# GR_Alim_Puissance.net
KiCad netlist of a schematic drawn in Altium Designer
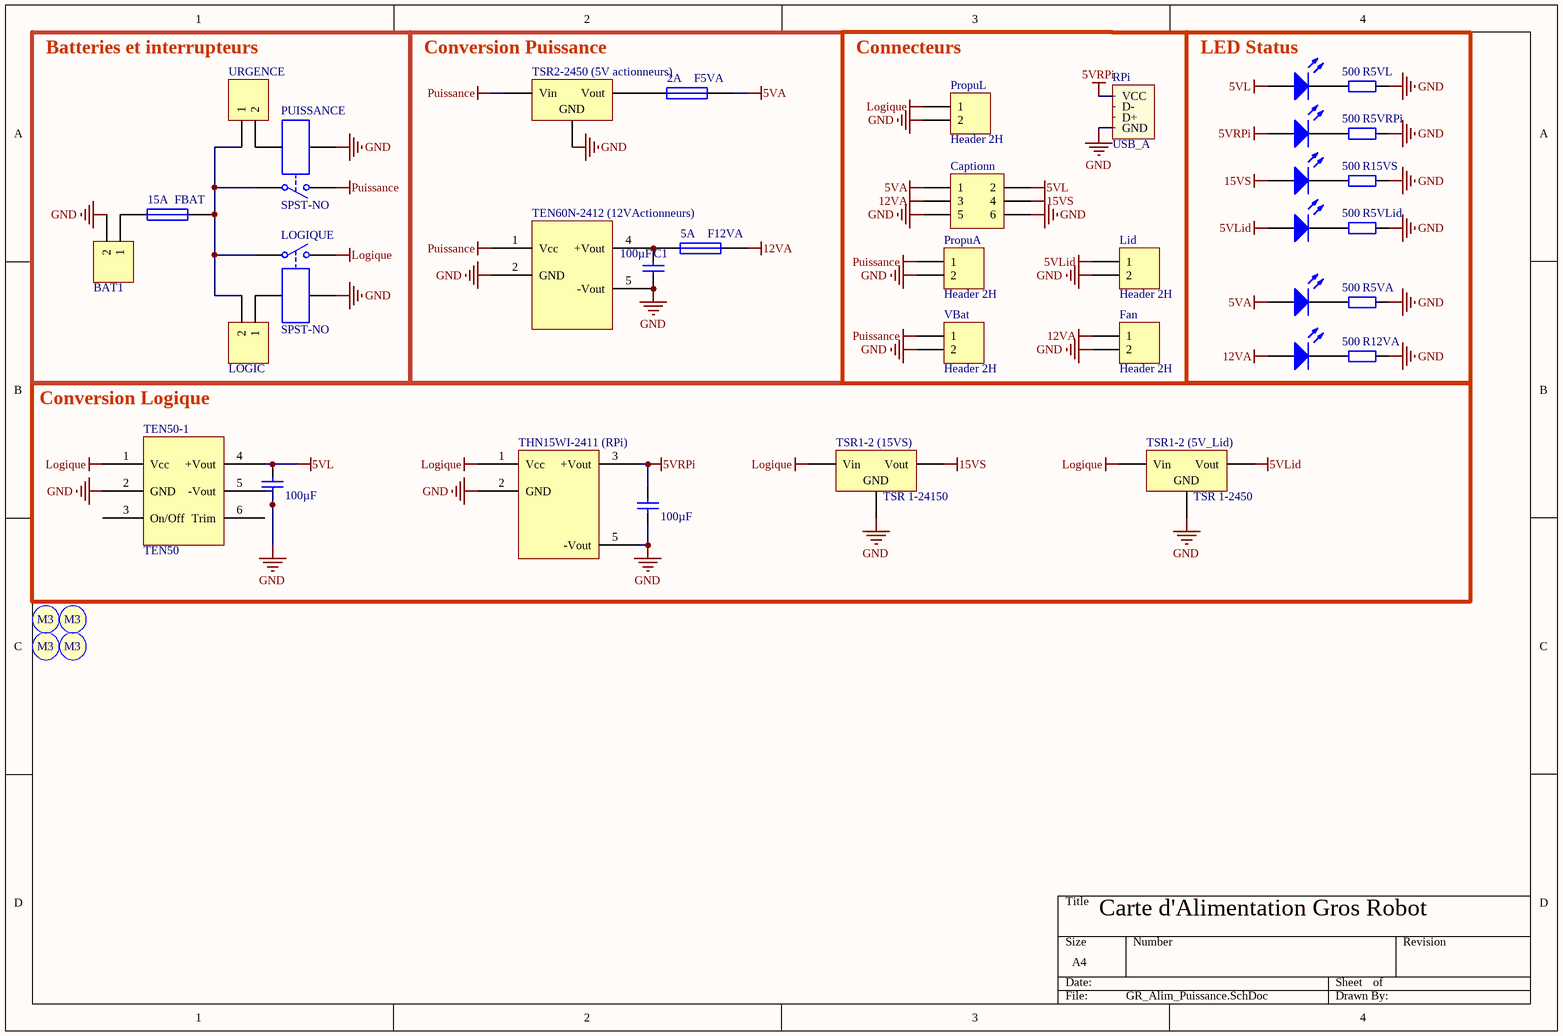
[diagram p0: GR_Alim_Puissance.SchDoc]

(export (version "E")
  (design (tool "Eeschema 10.0.6"))
  (components
    (comp (ref "BAT1")
      (value "Batterie 1")
      (footprint "Battery SALE")
      (description "Header, 2-Pin")
      (fields (field (name "PUBLISHER") "Altium Limited"))
      (libsource (lib "Miscellaneous Connectors") (part "Header 2"))
    )
    (comp (ref "C1")
      (value "100µF")
      (footprint "robot:Condensateur")
      (description "Capacitor")
      (fields (field (name "Comment") "Cap") (field (name "PUBLISHER") "Altium Limited"))
      (libsource (lib "Miscellaneous Devices") (part "Cap"))
    )
    (comp (ref "C10")
      (value "100µF")
      (footprint "robot:Condensateur")
      (description "Capacitor")
      (fields (field (name "Comment") "Cap") (field (name "PUBLISHER") "Altium Limited"))
      (libsource (lib "Miscellaneous Devices") (part "Cap"))
    )
    (comp (ref "C20")
      (value "100µF")
      (footprint "robot:Condensateur")
      (description "Capacitor")
      (fields (field (name "Comment") "Cap") (field (name "PUBLISHER") "Altium Limited"))
      (libsource (lib "Miscellaneous Devices") (part "Cap"))
    )
    (comp (ref "Captionn")
      (value "Header 3X2")
      (footprint "robot:MOLEX_MINIFITJR_3X2")
      (description "Header, 3-Pin, Dual row")
      (fields (field (name "PUBLISHER") "Altium Limited"))
      (libsource (lib "Miscellaneous Connectors") (part "Header 3X2"))
    )
    (comp (ref "D1")
      (value "LED Logique 5V")
      (footprint "3.2X1.6X1.1")
      (description "Typical RED, GREEN, YELLOW, AMBER GaAs LED")
      (fields (field (name "PUBLISHER") "Altium Limited"))
      (libsource (lib "Miscellaneous Devices") (part "LED2"))
    )
    (comp (ref "D2")
      (value "LED RPi 5V")
      (footprint "3.2X1.6X1.1")
      (description "Typical RED, GREEN, YELLOW, AMBER GaAs LED")
      (fields (field (name "PUBLISHER") "Altium Limited"))
      (libsource (lib "Miscellaneous Devices") (part "LED2"))
    )
    (comp (ref "D3")
      (value "LED Sonars 15V")
      (footprint "3.2X1.6X1.1")
      (description "Typical RED, GREEN, YELLOW, AMBER GaAs LED")
      (fields (field (name "PUBLISHER") "Altium Limited"))
      (libsource (lib "Miscellaneous Devices") (part "LED2"))
    )
    (comp (ref "D4")
      (value "LED Actionneurs 5V")
      (footprint "3.2X1.6X1.1")
      (description "Typical RED, GREEN, YELLOW, AMBER GaAs LED")
      (fields (field (name "PUBLISHER") "Altium Limited"))
      (libsource (lib "Miscellaneous Devices") (part "LED2"))
    )
    (comp (ref "D5")
      (value "LED Actionneurs 12V")
      (footprint "3.2X1.6X1.1")
      (description "Typical RED, GREEN, YELLOW, AMBER GaAs LED")
      (fields (field (name "PUBLISHER") "Altium Limited"))
      (libsource (lib "Miscellaneous Devices") (part "LED2"))
    )
    (comp (ref "D6")
      (value "LED Actionneurs 12V")
      (footprint "3.2X1.6X1.1")
      (description "Typical RED, GREEN, YELLOW, AMBER GaAs LED")
      (fields (field (name "PUBLISHER") "Altium Limited"))
      (libsource (lib "Miscellaneous Devices") (part "LED2"))
    )
    (comp (ref "F5VA")
      (value "2A")
      (footprint "robot:Fuse")
      (description "Fuse")
      (fields (field (name "PUBLISHER") "Altium Limited"))
      (libsource (lib "Miscellaneous Devices") (part "Fuse 1"))
    )
    (comp (ref "F12VA")
      (value "5A")
      (footprint "robot:Fuse")
      (description "Fuse")
      (fields (field (name "PUBLISHER") "Altium Limited"))
      (libsource (lib "Miscellaneous Devices") (part "Fuse 1"))
    )
    (comp (ref "Fan")
      (value "Header 2H")
      (footprint "robot:Molex SPOX 2x1H")
      (description "Header, 2-Pin, Right Angle")
      (fields (field (name "PUBLISHER") "Altium Limited"))
      (libsource (lib "Miscellaneous Connectors") (part "Header 2H"))
    )
    (comp (ref "FBAT")
      (value "15A")
      (footprint "robot:Fuse")
      (description "Fuse")
      (fields (field (name "PUBLISHER") "Altium Limited"))
      (libsource (lib "Miscellaneous Devices") (part "Fuse 1"))
    )
    (comp (ref "Lid")
      (value "Header 2H")
      (footprint "robot:Molex_MiniFitJr_2x1H")
      (description "Header, 2-Pin, Right Angle")
      (fields (field (name "PUBLISHER") "Altium Limited"))
      (libsource (lib "Miscellaneous Connectors") (part "Header 2H"))
    )
    (comp (ref "LOGIC")
      (value "Logic")
      (footprint "robot:MOLEX KK254 2X1H M")
      (description "Header, 2-Pin")
      (fields (field (name "PUBLISHER") "Altium Limited"))
      (libsource (lib "Miscellaneous Connectors") (part "Header 2"))
    )
    (comp (ref "LOGIQUE")
      (value "SPST-NO")
      (footprint "Relay")
      (description "OJ-SS-124LMH2,005")
      (fields (field (name "PUBLISHER") "Altium Limited"))
      (libsource (lib "Miscellaneous Devices") (part "Relay-SPST"))
    )
    (comp (ref "PropuA")
      (value "Header 2H")
      (footprint "robot:Molex_MiniFitJr_2x1H")
      (description "Header, 2-Pin, Right Angle")
      (fields (field (name "PUBLISHER") "Altium Limited"))
      (libsource (lib "Miscellaneous Connectors") (part "Header 2H"))
    )
    (comp (ref "PropuL")
      (value "Header 2H")
      (footprint "robot:Molex_MiniFitJr_2x1H")
      (description "Header, 2-Pin, Right Angle")
      (fields (field (name "PUBLISHER") "Altium Limited"))
      (libsource (lib "Miscellaneous Connectors") (part "Header 2H"))
    )
    (comp (ref "PUISSANCE")
      (value "SPST-NO")
      (footprint "Relay")
      (description "OJ-SS-124LMH2,005")
      (fields (field (name "PUBLISHER") "Altium Limited"))
      (libsource (lib "Miscellaneous Devices") (part "Relay-SPST"))
    )
    (comp (ref "R5VA")
      (value "500")
      (footprint "3.2X1.6X1.1")
      (description "Resistor")
      (fields (field (name "Comment") "Res4") (field (name "PUBLISHER") "Altium Limited"))
      (libsource (lib "Miscellaneous Devices") (part "Res2"))
    )
    (comp (ref "R5VL")
      (value "500")
      (footprint "3.2X1.6X1.1")
      (description "Resistor")
      (fields (field (name "Comment") "Res1") (field (name "PUBLISHER") "Altium Limited"))
      (libsource (lib "Miscellaneous Devices") (part "Res2"))
    )
    (comp (ref "R5VLid")
      (value "500")
      (footprint "3.2X1.6X1.1")
      (description "Resistor")
      (fields (field (name "Comment") "Res5") (field (name "PUBLISHER") "Altium Limited"))
      (libsource (lib "Miscellaneous Devices") (part "Res2"))
    )
    (comp (ref "R5VRPi")
      (value "500")
      (footprint "3.2X1.6X1.1")
      (description "Resistor")
      (fields (field (name "Comment") "Res2") (field (name "PUBLISHER") "Altium Limited"))
      (libsource (lib "Miscellaneous Devices") (part "Res2"))
    )
    (comp (ref "R12VA")
      (value "500")
      (footprint "3.2X1.6X1.1")
      (description "Resistor")
      (fields (field (name "Comment") "Res5") (field (name "PUBLISHER") "Altium Limited"))
      (libsource (lib "Miscellaneous Devices") (part "Res2"))
    )
    (comp (ref "R15VS")
      (value "500")
      (footprint "3.2X1.6X1.1")
      (description "Resistor")
      (fields (field (name "Comment") "Res3") (field (name "PUBLISHER") "Altium Limited"))
      (libsource (lib "Miscellaneous Devices") (part "Res2"))
    )
    (comp (ref "RPi")
      (value "USB_A")
      (footprint "robot:USB Connector")
      (libsource (lib "robot") (part "USB_A"))
    )
    (comp (ref "S1")
      (value "Screw M3")
      (footprint "Robot_2019:Screw M3")
      (libsource (lib "Robot_2019") (part "Screw M3"))
    )
    (comp (ref "S2")
      (value "Screw M3")
      (footprint "Robot_2019:Screw M3")
      (libsource (lib "Robot_2019") (part "Screw M3"))
    )
    (comp (ref "S3")
      (value "Screw M3")
      (footprint "Robot_2019:Screw M3")
      (libsource (lib "Robot_2019") (part "Screw M3"))
    )
    (comp (ref "S4")
      (value "Screw M3")
      (footprint "Robot_2019:Screw M3")
      (libsource (lib "Robot_2019") (part "Screw M3"))
    )
    (comp (ref "TEN50-1")
      (value "TEN50")
      (footprint "robot:TRACO_1x1inch")
      (description "TRACO TEN50")
      (fields (field (name "PUBLISHER") "Altium Limited"))
      (libsource (lib "robot") (part "TEN50"))
    )
    (comp (ref "TEN60N-1")
      (value "TEN60N-2412 (12VActionneurs)")
      (footprint "Robot:TRACO_2x1inch")
      (description "TRACO TEN60N")
      (fields (field (name "PUBLISHER") "Altium Limited"))
      (libsource (lib "TracoLib") (part "TEN60N"))
    )
    (comp (ref "THN15-5")
      (value "THN15WI-2411 (RPi)")
      (footprint "Robot:TRACO_1x1inch")
      (fields (field (name "PUBLISHER") "Altium Limited"))
      (libsource (lib "TracoLib") (part "THN15WI"))
    )
    (comp (ref "TSR1-2 (5V_Lid)")
      (value "TSR 1-2450")
      (footprint "robot:TRS")
      (description "Voltage Regulator")
      (fields (field (name "PUBLISHER") "Altium Limited"))
      (libsource (lib "Miscellaneous Devices") (part "Volt Reg"))
    )
    (comp (ref "TSR1-2 (15VS)")
      (value "TSR 1-24150")
      (footprint "robot:TRS")
      (description "Voltage Regulator")
      (fields (field (name "PUBLISHER") "Altium Limited"))
      (libsource (lib "Miscellaneous Devices") (part "Volt Reg"))
    )
    (comp (ref "TSR2-1")
      (value "TSR2-2450 (5V actionneurs)")
      (footprint "robot:TRS - centered")
      (description "Voltage Regulator")
      (fields (field (name "PUBLISHER") "Altium Limited"))
      (libsource (lib "Miscellaneous Devices") (part "Volt Reg"))
    )
    (comp (ref "URGENCE")
      (value "Urgence")
      (footprint "robot:MOLEX KK254 2X1H M")
      (description "Header, 2-Pin")
      (fields (field (name "PUBLISHER") "Altium Limited"))
      (libsource (lib "") (part "Header 2_1"))
    )
    (comp (ref "VBat")
      (value "Header 2H")
      (footprint "robot:Molex_MiniFitJr_2x1H")
      (description "Header, 2-Pin, Right Angle")
      (fields (field (name "PUBLISHER") "Altium Limited"))
      (libsource (lib "Miscellaneous Connectors") (part "Header 2H"))
    )
  )
  (nets
    (net (code "1") (name "5VA") (class "Default")
      (node (ref "Captionn") (pin "1") (pinfunction "1_1") (pintype "passive"))
      (node (ref "D4") (pin "1") (pinfunction "A_1") (pintype "passive"))
      (node (ref "F5VA") (pin "2") (pinfunction "2_2") (pintype "passive"))
    )
    (net (code "2") (name "5VL") (class "Default")
      (node (ref "C20") (pin "1") (pinfunction "1_1") (pintype "passive"))
      (node (ref "Captionn") (pin "2") (pinfunction "2_2") (pintype "passive"))
      (node (ref "D1") (pin "1") (pinfunction "A_1") (pintype "passive"))
      (node (ref "TEN50-1") (pin "4") (pinfunction "+Vout_4") (pintype "passive"))
    )
    (net (code "3") (name "5VLid") (class "Default")
      (node (ref "D6") (pin "1") (pinfunction "A_1") (pintype "passive"))
      (node (ref "Lid") (pin "1") (pinfunction "1_1") (pintype "passive"))
      (node (ref "TSR1-2 (5V_Lid)") (pin "3") (pinfunction "Vout_3") (pintype "passive"))
    )
    (net (code "4") (name "5VRPi") (class "Default")
      (node (ref "C10") (pin "1") (pinfunction "1_1") (pintype "passive"))
      (node (ref "D2") (pin "1") (pinfunction "A_1") (pintype "passive"))
      (node (ref "RPi") (pin "1") (pinfunction "VCC_1") (pintype "passive"))
      (node (ref "THN15-5") (pin "3") (pinfunction "+Vout_3") (pintype "passive"))
    )
    (net (code "5") (name "12VA") (class "Default")
      (node (ref "Captionn") (pin "3") (pinfunction "3_3") (pintype "passive"))
      (node (ref "D5") (pin "1") (pinfunction "A_1") (pintype "passive"))
      (node (ref "F12VA") (pin "2") (pinfunction "2_2") (pintype "passive"))
      (node (ref "Fan") (pin "1") (pinfunction "1_1") (pintype "passive"))
    )
    (net (code "6") (name "15VS") (class "Default")
      (node (ref "Captionn") (pin "4") (pinfunction "4_4") (pintype "passive"))
      (node (ref "D3") (pin "1") (pinfunction "A_1") (pintype "passive"))
      (node (ref "TSR1-2 (15VS)") (pin "3") (pinfunction "Vout_3") (pintype "passive"))
    )
    (net (code "7") (name "GND") (class "Default")
      (node (ref "BAT1") (pin "2") (pinfunction "2_2") (pintype "passive"))
      (node (ref "C1") (pin "1") (pinfunction "1_1") (pintype "passive"))
      (node (ref "C10") (pin "2") (pinfunction "2_2") (pintype "passive"))
      (node (ref "C20") (pin "2") (pinfunction "2_2") (pintype "passive"))
      (node (ref "Captionn") (pin "5") (pinfunction "5_5") (pintype "passive"))
      (node (ref "Captionn") (pin "6") (pinfunction "6_6") (pintype "passive"))
      (node (ref "Fan") (pin "2") (pinfunction "2_2") (pintype "passive"))
      (node (ref "LOGIQUE") (pin "4") (pinfunction "4_4") (pintype "passive"))
      (node (ref "Lid") (pin "2") (pinfunction "2_2") (pintype "passive"))
      (node (ref "PUISSANCE") (pin "4") (pinfunction "4_4") (pintype "passive"))
      (node (ref "PropuA") (pin "2") (pinfunction "2_2") (pintype "passive"))
      (node (ref "PropuL") (pin "2") (pinfunction "2_2") (pintype "passive"))
      (node (ref "R12VA") (pin "2") (pinfunction "2_2") (pintype "passive"))
      (node (ref "R15VS") (pin "2") (pinfunction "2_2") (pintype "passive"))
      (node (ref "R5VA") (pin "2") (pinfunction "2_2") (pintype "passive"))
      (node (ref "R5VL") (pin "2") (pinfunction "2_2") (pintype "passive"))
      (node (ref "R5VLid") (pin "2") (pinfunction "2_2") (pintype "passive"))
      (node (ref "R5VRPi") (pin "2") (pinfunction "2_2") (pintype "passive"))
      (node (ref "RPi") (pin "4") (pinfunction "GND_4") (pintype "passive"))
      (node (ref "TEN50-1") (pin "2") (pinfunction "GND_2") (pintype "passive"))
      (node (ref "TEN50-1") (pin "5") (pinfunction "-Vout_5") (pintype "passive"))
      (node (ref "TEN60N-1") (pin "2") (pinfunction "GND_2") (pintype "passive"))
      (node (ref "TEN60N-1") (pin "5") (pinfunction "-Vout_5") (pintype "passive"))
      (node (ref "THN15-5") (pin "2") (pinfunction "GND_2") (pintype "passive"))
      (node (ref "THN15-5") (pin "5") (pinfunction "-Vout_5") (pintype "passive"))
      (node (ref "TSR1-2 (15VS)") (pin "2") (pinfunction "GND_2") (pintype "passive"))
      (node (ref "TSR1-2 (5V_Lid)") (pin "2") (pinfunction "GND_2") (pintype "passive"))
      (node (ref "TSR2-1") (pin "2") (pinfunction "GND_2") (pintype "passive"))
      (node (ref "VBat") (pin "2") (pinfunction "2_2") (pintype "passive"))
    )
    (net (code "8") (name "Logique") (class "Default")
      (node (ref "LOGIQUE") (pin "2") (pinfunction "2_2") (pintype "passive"))
      (node (ref "PropuL") (pin "1") (pinfunction "1_1") (pintype "passive"))
      (node (ref "TEN50-1") (pin "1") (pinfunction "Vcc_1") (pintype "passive"))
      (node (ref "THN15-5") (pin "1") (pinfunction "Vcc_1") (pintype "passive"))
      (node (ref "TSR1-2 (15VS)") (pin "1") (pinfunction "Vin_1") (pintype "passive"))
      (node (ref "TSR1-2 (5V_Lid)") (pin "1") (pinfunction "Vin_1") (pintype "passive"))
    )
    (net (code "9") (name "Net-(BAT1-Pad1)") (class "Default")
      (node (ref "BAT1") (pin "1") (pinfunction "1_1") (pintype "passive"))
      (node (ref "FBAT") (pin "1") (pinfunction "1_1") (pintype "passive"))
    )
    (net (code "10") (name "Net-(D1-K)") (class "Default")
      (node (ref "D1") (pin "2") (pinfunction "K_2") (pintype "passive"))
      (node (ref "R5VL") (pin "1") (pinfunction "1_1") (pintype "passive"))
    )
    (net (code "11") (name "Net-(D2-K)") (class "Default")
      (node (ref "D2") (pin "2") (pinfunction "K_2") (pintype "passive"))
      (node (ref "R5VRPi") (pin "1") (pinfunction "1_1") (pintype "passive"))
    )
    (net (code "12") (name "Net-(D3-K)") (class "Default")
      (node (ref "D3") (pin "2") (pinfunction "K_2") (pintype "passive"))
      (node (ref "R15VS") (pin "1") (pinfunction "1_1") (pintype "passive"))
    )
    (net (code "13") (name "Net-(D4-K)") (class "Default")
      (node (ref "D4") (pin "2") (pinfunction "K_2") (pintype "passive"))
      (node (ref "R5VA") (pin "1") (pinfunction "1_1") (pintype "passive"))
    )
    (net (code "14") (name "Net-(D5-K)") (class "Default")
      (node (ref "D5") (pin "2") (pinfunction "K_2") (pintype "passive"))
      (node (ref "R12VA") (pin "1") (pinfunction "1_1") (pintype "passive"))
    )
    (net (code "15") (name "Net-(D6-K)") (class "Default")
      (node (ref "D6") (pin "2") (pinfunction "K_2") (pintype "passive"))
      (node (ref "R5VLid") (pin "1") (pinfunction "1_1") (pintype "passive"))
    )
    (net (code "16") (name "Net-(FBAT-Pad2)") (class "Default")
      (node (ref "FBAT") (pin "2") (pinfunction "2_2") (pintype "passive"))
      (node (ref "LOGIC") (pin "2") (pinfunction "2_2") (pintype "passive"))
      (node (ref "LOGIQUE") (pin "1") (pinfunction "1_1") (pintype "passive"))
      (node (ref "PUISSANCE") (pin "1") (pinfunction "1_1") (pintype "passive"))
      (node (ref "URGENCE") (pin "1") (pinfunction "1_1") (pintype "passive"))
    )
    (net (code "17") (name "Net-(LOGIC-Pad1)") (class "Default")
      (node (ref "LOGIC") (pin "1") (pinfunction "1_1") (pintype "passive"))
      (node (ref "LOGIQUE") (pin "3") (pinfunction "3_3") (pintype "passive"))
    )
    (net (code "18") (name "Net-(PUISSANCE-Pad3)") (class "Default")
      (node (ref "PUISSANCE") (pin "3") (pinfunction "3_3") (pintype "passive"))
      (node (ref "URGENCE") (pin "2") (pinfunction "2_2") (pintype "passive"))
    )
    (net (code "19") (name "Net-(TEN60N-1-+Vout)") (class "Default")
      (node (ref "C1") (pin "2") (pinfunction "2_2") (pintype "passive"))
      (node (ref "F12VA") (pin "1") (pinfunction "1_1") (pintype "passive"))
      (node (ref "TEN60N-1") (pin "4") (pinfunction "+Vout_4") (pintype "passive"))
    )
    (net (code "20") (name "Net-(TSR2-1-Vout)") (class "Default")
      (node (ref "F5VA") (pin "1") (pinfunction "1_1") (pintype "passive"))
      (node (ref "TSR2-1") (pin "3") (pinfunction "Vout_3") (pintype "passive"))
    )
    (net (code "21") (name "Puissance") (class "Default")
      (node (ref "PUISSANCE") (pin "2") (pinfunction "2_2") (pintype "passive"))
      (node (ref "PropuA") (pin "1") (pinfunction "1_1") (pintype "passive"))
      (node (ref "TEN60N-1") (pin "1") (pinfunction "Vcc_1") (pintype "passive"))
      (node (ref "TSR2-1") (pin "1") (pinfunction "Vin_1") (pintype "passive"))
      (node (ref "VBat") (pin "1") (pinfunction "1_1") (pintype "passive"))
    )
    (net (code "22") (name "unconnected-(RPi-D+-Pad3)") (class "Default")
      (node (ref "RPi") (pin "3") (pinfunction "D+_3") (pintype "passive"))
    )
    (net (code "23") (name "unconnected-(RPi-D--Pad2)") (class "Default")
      (node (ref "RPi") (pin "2") (pinfunction "D-_2") (pintype "passive"))
    )
    (net (code "24") (name "unconnected-(TEN50-1-On{slash}Off-Pad3)") (class "Default")
      (node (ref "TEN50-1") (pin "3") (pinfunction "On/Off_3") (pintype "passive"))
    )
    (net (code "25") (name "unconnected-(TEN50-1-Trim-Pad6)") (class "Default")
      (node (ref "TEN50-1") (pin "6") (pinfunction "Trim_6") (pintype "passive"))
    )
    (net (code "26") (name "unconnected-(TEN60N-1-On{slash}Off-Pad3)") (class "Default")
      (node (ref "TEN60N-1") (pin "3") (pinfunction "On/Off_3") (pintype "passive"))
    )
    (net (code "27") (name "unconnected-(TEN60N-1-Trim-Pad6)") (class "Default")
      (node (ref "TEN60N-1") (pin "6") (pinfunction "Trim_6") (pintype "passive"))
    )
    (net (code "28") (name "unconnected-(THN15-5-On{slash}Off-Pad6)") (class "Default")
      (node (ref "THN15-5") (pin "6") (pinfunction "On/Off_6") (pintype "passive"))
    )
    (net (code "29") (name "unconnected-(THN15-5-Trim-Pad4)") (class "Default")
      (node (ref "THN15-5") (pin "4") (pinfunction "Trim_4") (pintype "passive"))
    )
  )
)
